# controllerv2e.net
KiCad netlist of a schematic drawn in EAGLE
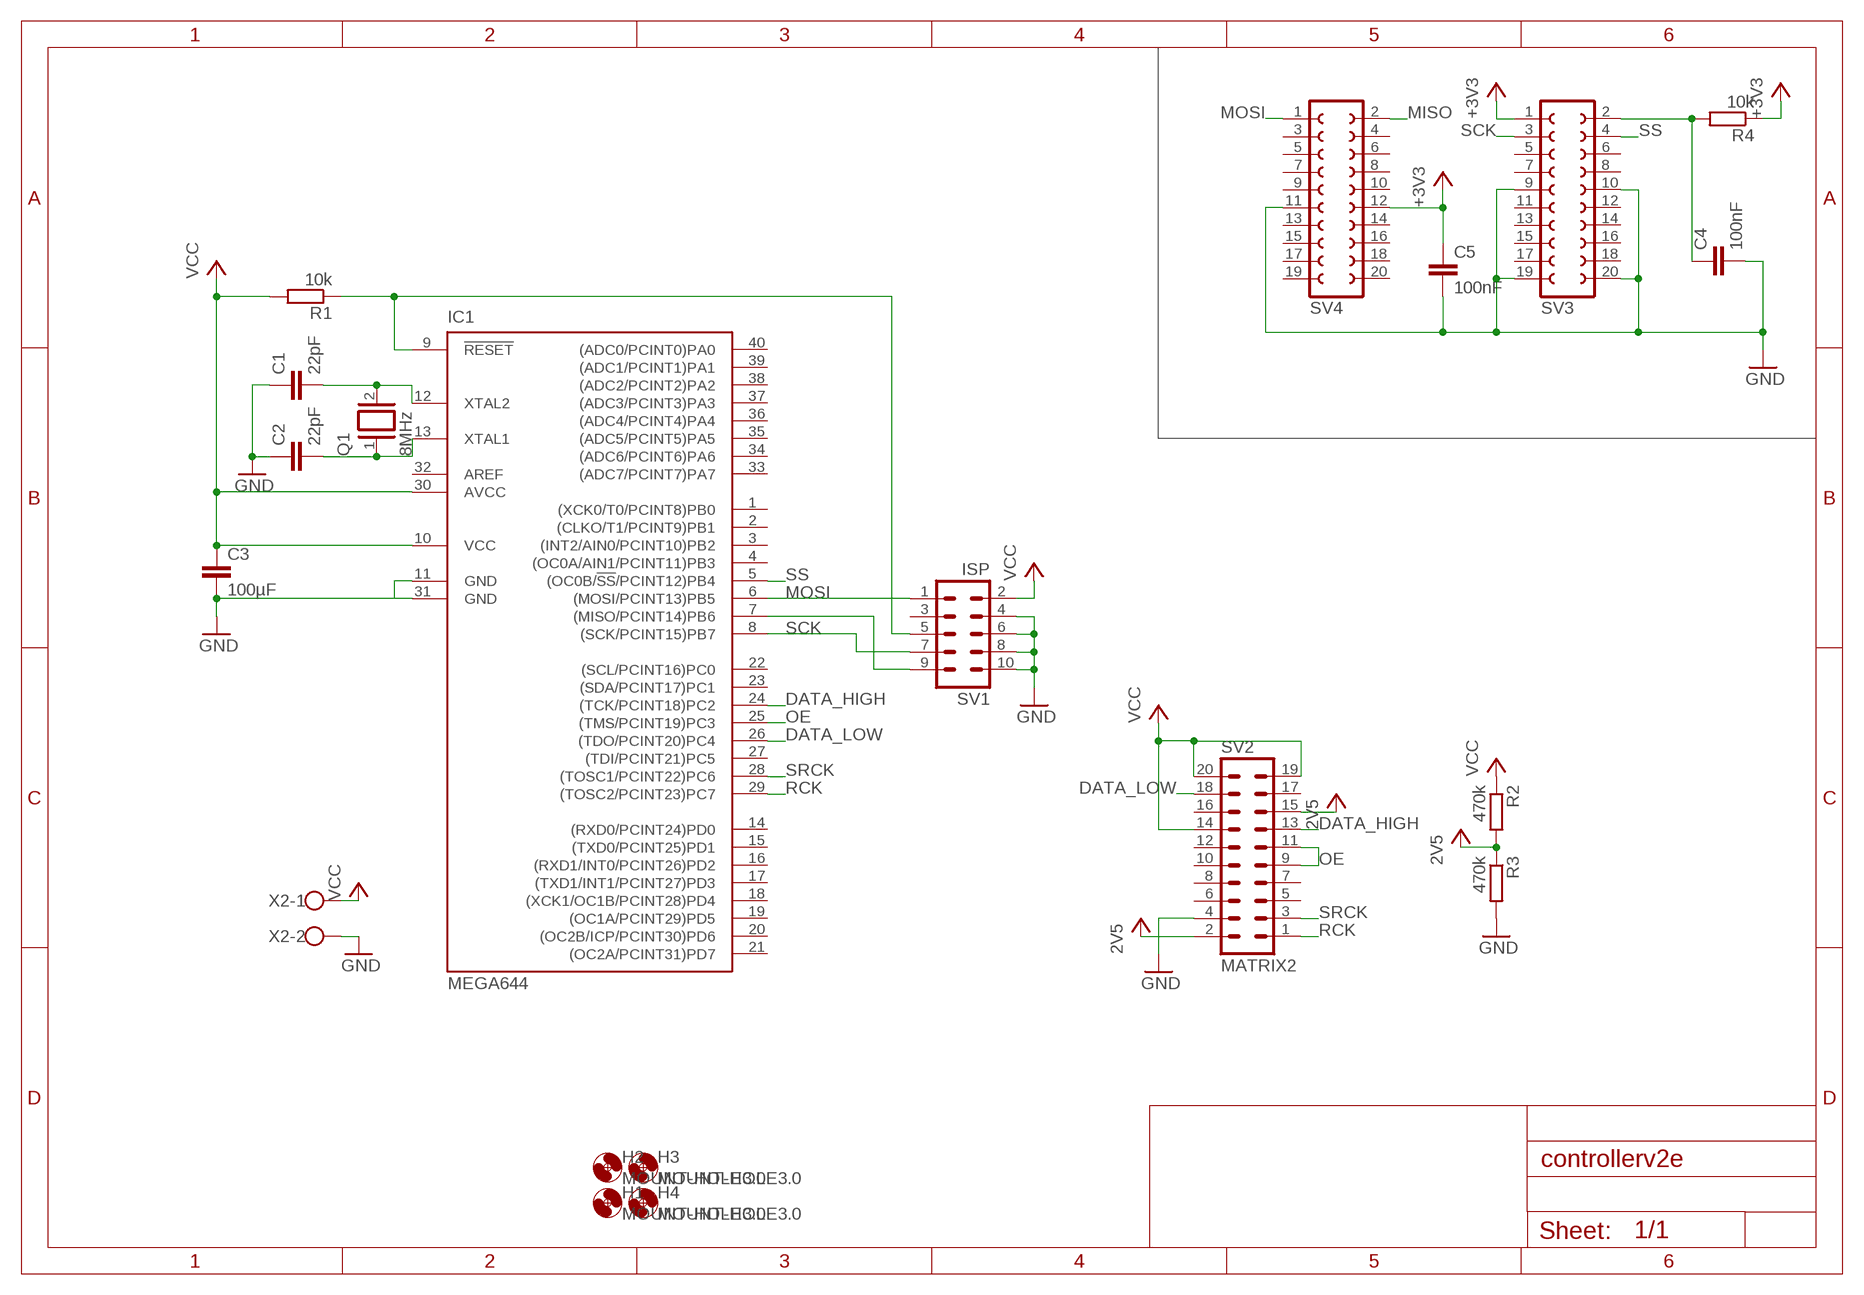
[diagram p0: schematic, sheet 1]

(export (version "E")
  (design (tool "Eeschema 10.0.6"))
  (components
    (comp (ref "C1")
      (value "22pF")
      (footprint "eagle-import:C050-024X044")
      (libsource (lib "eagle-import") (part "C-EU050-024X044"))
    )
    (comp (ref "C2")
      (value "22pF")
      (footprint "eagle-import:C050-024X044")
      (libsource (lib "eagle-import") (part "C-EU050-024X044"))
    )
    (comp (ref "C3")
      (value "100µF")
      (footprint "eagle-import:C050-030X075")
      (libsource (lib "eagle-import") (part "C-EU050-030X075"))
    )
    (comp (ref "C4")
      (value "100nF")
      (footprint "eagle-import:C050-024X044")
      (libsource (lib "eagle-import") (part "C-EU050-024X044"))
    )
    (comp (ref "C5")
      (value "100nF")
      (footprint "eagle-import:C050-024X044")
      (libsource (lib "eagle-import") (part "C-EU050-024X044"))
    )
    (comp (ref "H1")
      (value "MOUNT-HOLE3.0")
      (footprint "eagle-import:3,0")
      (libsource (lib "eagle-import") (part "MOUNT-HOLE3.0"))
    )
    (comp (ref "H2")
      (value "MOUNT-HOLE3.0")
      (footprint "eagle-import:3,0")
      (libsource (lib "eagle-import") (part "MOUNT-HOLE3.0"))
    )
    (comp (ref "H3")
      (value "MOUNT-HOLE3.0")
      (footprint "eagle-import:3,0")
      (libsource (lib "eagle-import") (part "MOUNT-HOLE3.0"))
    )
    (comp (ref "H4")
      (value "MOUNT-HOLE3.0")
      (footprint "eagle-import:3,0")
      (libsource (lib "eagle-import") (part "MOUNT-HOLE3.0"))
    )
    (comp (ref "IC1")
      (value "MEGA644")
      (footprint "eagle-import:DIL40")
      (libsource (lib "eagle-import") (part "MEGA164P/324P/644P-PU"))
    )
    (comp (ref "Q1")
      (value "8MHz")
      (footprint "eagle-import:QS")
      (libsource (lib "eagle-import") (part "XTAL/S"))
    )
    (comp (ref "R1")
      (value "10k")
      (footprint "eagle-import:0207_10")
      (libsource (lib "eagle-import") (part "R-EU_0207/10"))
    )
    (comp (ref "R2")
      (value "470k")
      (footprint "eagle-import:0207_10")
      (libsource (lib "eagle-import") (part "R-EU_0207/10"))
    )
    (comp (ref "R3")
      (value "470k")
      (footprint "eagle-import:0207_10")
      (libsource (lib "eagle-import") (part "R-EU_0207/10"))
    )
    (comp (ref "R4")
      (value "10k")
      (footprint "eagle-import:0207_10")
      (libsource (lib "eagle-import") (part "R-EU_0207/10"))
    )
    (comp (ref "SV1")
      (value "ISP")
      (footprint "eagle-import:ML10")
      (libsource (lib "eagle-import") (part "ML10"))
    )
    (comp (ref "SV2")
      (value "MATRIX2")
      (footprint "eagle-import:ML20")
      (libsource (lib "eagle-import") (part "ML20"))
    )
    (comp (ref "SV3")
      (value "FE10-2")
      (footprint "eagle-import:FE10-2")
      (libsource (lib "eagle-import") (part "FE10-2"))
    )
    (comp (ref "SV4")
      (value "FE10-2")
      (footprint "eagle-import:FE10-2")
      (libsource (lib "eagle-import") (part "FE10-2"))
    )
    (comp (ref "X2")
      (value "GND")
      (footprint "eagle-import:W237-102")
      (fields (field (name "MPN") "237-102"))
      (libsource (lib "eagle-import") (part "W237-102"))
    )
  )
  (nets
    (net (code "1") (name "+3V3") (class "Default")
      (node (ref "C5") (pin "1") (pinfunction "1_1") (pintype "passive"))
      (node (ref "R2") (pin "2") (pinfunction "2_2") (pintype "passive"))
      (node (ref "R3") (pin "1") (pinfunction "1_1") (pintype "passive"))
      (node (ref "R4") (pin "1") (pinfunction "1_1") (pintype "passive"))
      (node (ref "SV2") (pin "15") (pinfunction "15_15") (pintype "passive"))
      (node (ref "SV2") (pin "2") (pinfunction "2_2") (pintype "passive"))
      (node (ref "SV3") (pin "1") (pinfunction "1_1") (pintype "passive"))
      (node (ref "SV4") (pin "12") (pinfunction "12_12") (pintype "passive"))
    )
    (net (code "2") (name "/AREF") (class "Default")
      (node (ref "IC1") (pin "32") (pinfunction "AREF_32") (pintype "power_in"))
    )
    (net (code "3") (name "/DATA_HIGH") (class "Default")
      (node (ref "IC1") (pin "24") (pinfunction "(TCK/PCINT18)PC2_24") (pintype "bidirectional"))
      (node (ref "SV2") (pin "13") (pinfunction "13_13") (pintype "passive"))
    )
    (net (code "4") (name "/DATA_LOW") (class "Default")
      (node (ref "IC1") (pin "26") (pinfunction "(TDO/PCINT20)PC4_26") (pintype "bidirectional"))
      (node (ref "SV2") (pin "18") (pinfunction "18_18") (pintype "passive"))
    )
    (net (code "5") (name "/MISO") (class "Default")
      (node (ref "SV4") (pin "2") (pinfunction "2_2") (pintype "passive"))
    )
    (net (code "6") (name "/MOSI") (class "Default")
      (node (ref "IC1") (pin "6") (pinfunction "(MOSI/PCINT13)PB5_6") (pintype "bidirectional"))
      (node (ref "SV1") (pin "1") (pinfunction "1_1") (pintype "passive"))
      (node (ref "SV4") (pin "1") (pinfunction "1_1") (pintype "passive"))
    )
    (net (code "7") (name "/OE") (class "Default")
      (node (ref "IC1") (pin "25") (pinfunction "(TMS/PCINT19)PC3_25") (pintype "bidirectional"))
      (node (ref "SV2") (pin "11") (pinfunction "11_11") (pintype "passive"))
      (node (ref "SV2") (pin "9") (pinfunction "9_9") (pintype "passive"))
    )
    (net (code "8") (name "/RCK") (class "Default")
      (node (ref "IC1") (pin "29") (pinfunction "(TOSC2/PCINT23)PC7_29") (pintype "bidirectional"))
      (node (ref "SV2") (pin "1") (pinfunction "1_1") (pintype "passive"))
    )
    (net (code "9") (name "/SCK") (class "Default")
      (node (ref "IC1") (pin "8") (pinfunction "(SCK/PCINT15)PB7_8") (pintype "bidirectional"))
      (node (ref "SV1") (pin "7") (pinfunction "7_7") (pintype "passive"))
      (node (ref "SV3") (pin "3") (pinfunction "3_3") (pintype "passive"))
    )
    (net (code "10") (name "/SRCK") (class "Default")
      (node (ref "IC1") (pin "28") (pinfunction "(TOSC1/PCINT22)PC6_28") (pintype "bidirectional"))
      (node (ref "SV2") (pin "3") (pinfunction "3_3") (pintype "passive"))
    )
    (net (code "11") (name "/SS") (class "Default")
      (node (ref "IC1") (pin "5") (pinfunction "(OC0B/~{SS}/PCINT12)PB4_5") (pintype "bidirectional"))
      (node (ref "SV3") (pin "4") (pinfunction "4_4") (pintype "passive"))
    )
    (net (code "12") (name "GND") (class "Default")
      (node (ref "C1") (pin "1") (pinfunction "1_1") (pintype "passive"))
      (node (ref "C2") (pin "1") (pinfunction "1_1") (pintype "passive"))
      (node (ref "C3") (pin "2") (pinfunction "2_2") (pintype "passive"))
      (node (ref "C4") (pin "2") (pinfunction "2_2") (pintype "passive"))
      (node (ref "C5") (pin "2") (pinfunction "2_2") (pintype "passive"))
      (node (ref "IC1") (pin "11") (pinfunction "GND_11") (pintype "power_in"))
      (node (ref "IC1") (pin "31") (pinfunction "GND_31") (pintype "power_in"))
      (node (ref "R3") (pin "2") (pinfunction "2_2") (pintype "passive"))
      (node (ref "SV1") (pin "10") (pinfunction "10_10") (pintype "passive"))
      (node (ref "SV1") (pin "4") (pinfunction "4_4") (pintype "passive"))
      (node (ref "SV1") (pin "6") (pinfunction "6_6") (pintype "passive"))
      (node (ref "SV1") (pin "8") (pinfunction "8_8") (pintype "passive"))
      (node (ref "SV2") (pin "4") (pinfunction "4_4") (pintype "passive"))
      (node (ref "SV3") (pin "10") (pinfunction "10_10") (pintype "passive"))
      (node (ref "SV3") (pin "19") (pinfunction "19_19") (pintype "passive"))
      (node (ref "SV3") (pin "20") (pinfunction "20_20") (pintype "passive"))
      (node (ref "SV3") (pin "9") (pinfunction "9_9") (pintype "passive"))
      (node (ref "SV4") (pin "11") (pinfunction "11_11") (pintype "passive"))
      (node (ref "X2") (pin "2") (pinfunction "KL_2") (pintype "passive"))
    )
    (net (code "13") (name "Net-(C4-Pad1)") (class "Default")
      (node (ref "C4") (pin "1") (pinfunction "1_1") (pintype "passive"))
      (node (ref "R4") (pin "2") (pinfunction "2_2") (pintype "passive"))
      (node (ref "SV3") (pin "2") (pinfunction "2_2") (pintype "passive"))
    )
    (net (code "14") (name "Net-(IC1-(MISO{slash}PCINT14)PB6)") (class "Default")
      (node (ref "IC1") (pin "7") (pinfunction "(MISO/PCINT14)PB6_7") (pintype "bidirectional"))
      (node (ref "SV1") (pin "9") (pinfunction "9_9") (pintype "passive"))
    )
    (net (code "15") (name "Net-(IC1-XTAL1)") (class "Default")
      (node (ref "C2") (pin "2") (pinfunction "2_2") (pintype "passive"))
      (node (ref "IC1") (pin "13") (pinfunction "XTAL1_13") (pintype "input"))
      (node (ref "Q1") (pin "1") (pinfunction "1_1") (pintype "passive"))
    )
    (net (code "16") (name "Net-(IC1-XTAL2)") (class "Default")
      (node (ref "C1") (pin "2") (pinfunction "2_2") (pintype "passive"))
      (node (ref "IC1") (pin "12") (pinfunction "XTAL2_12") (pintype "output"))
      (node (ref "Q1") (pin "2") (pinfunction "2_2") (pintype "passive"))
    )
    (net (code "17") (name "Net-(IC1-~{RESET})") (class "Default")
      (node (ref "IC1") (pin "9") (pinfunction "~{RESET}_9") (pintype "input"))
      (node (ref "R1") (pin "1") (pinfunction "1_1") (pintype "passive"))
      (node (ref "SV1") (pin "5") (pinfunction "5_5") (pintype "passive"))
    )
    (net (code "18") (name "VCC") (class "Default")
      (node (ref "C3") (pin "1") (pinfunction "1_1") (pintype "passive"))
      (node (ref "IC1") (pin "10") (pinfunction "VCC_10") (pintype "power_in"))
      (node (ref "IC1") (pin "30") (pinfunction "AVCC_30") (pintype "power_in"))
      (node (ref "R1") (pin "2") (pinfunction "2_2") (pintype "passive"))
      (node (ref "R2") (pin "1") (pinfunction "1_1") (pintype "passive"))
      (node (ref "SV1") (pin "2") (pinfunction "2_2") (pintype "passive"))
      (node (ref "SV2") (pin "14") (pinfunction "14_14") (pintype "passive"))
      (node (ref "SV2") (pin "19") (pinfunction "19_19") (pintype "passive"))
      (node (ref "SV2") (pin "20") (pinfunction "20_20") (pintype "passive"))
      (node (ref "X2") (pin "1") (pinfunction "KL_1") (pintype "passive"))
    )
    (net (code "19") (name "unconnected-(IC1-(ADC0{slash}PCINT0)PA0-Pad40)") (class "Default")
      (node (ref "IC1") (pin "40") (pinfunction "(ADC0/PCINT0)PA0_40") (pintype "bidirectional"))
    )
    (net (code "20") (name "unconnected-(IC1-(ADC1{slash}PCINT1)PA1-Pad39)") (class "Default")
      (node (ref "IC1") (pin "39") (pinfunction "(ADC1/PCINT1)PA1_39") (pintype "bidirectional"))
    )
    (net (code "21") (name "unconnected-(IC1-(ADC2{slash}PCINT2)PA2-Pad38)") (class "Default")
      (node (ref "IC1") (pin "38") (pinfunction "(ADC2/PCINT2)PA2_38") (pintype "bidirectional"))
    )
    (net (code "22") (name "unconnected-(IC1-(ADC3{slash}PCINT3)PA3-Pad37)") (class "Default")
      (node (ref "IC1") (pin "37") (pinfunction "(ADC3/PCINT3)PA3_37") (pintype "bidirectional"))
    )
    (net (code "23") (name "unconnected-(IC1-(ADC4{slash}PCINT4)PA4-Pad36)") (class "Default")
      (node (ref "IC1") (pin "36") (pinfunction "(ADC4/PCINT4)PA4_36") (pintype "bidirectional"))
    )
    (net (code "24") (name "unconnected-(IC1-(ADC5{slash}PCINT5)PA5-Pad35)") (class "Default")
      (node (ref "IC1") (pin "35") (pinfunction "(ADC5/PCINT5)PA5_35") (pintype "bidirectional"))
    )
    (net (code "25") (name "unconnected-(IC1-(ADC6{slash}PCINT6)PA6-Pad34)") (class "Default")
      (node (ref "IC1") (pin "34") (pinfunction "(ADC6/PCINT6)PA6_34") (pintype "bidirectional"))
    )
    (net (code "26") (name "unconnected-(IC1-(ADC7{slash}PCINT7)PA7-Pad33)") (class "Default")
      (node (ref "IC1") (pin "33") (pinfunction "(ADC7/PCINT7)PA7_33") (pintype "bidirectional"))
    )
    (net (code "27") (name "unconnected-(IC1-(CLKO{slash}T1{slash}PCINT9)PB1-Pad2)") (class "Default")
      (node (ref "IC1") (pin "2") (pinfunction "(CLKO/T1/PCINT9)PB1_2") (pintype "bidirectional"))
    )
    (net (code "28") (name "unconnected-(IC1-(INT2{slash}AIN0{slash}PCINT10)PB2-Pad3)") (class "Default")
      (node (ref "IC1") (pin "3") (pinfunction "(INT2/AIN0/PCINT10)PB2_3") (pintype "bidirectional"))
    )
    (net (code "29") (name "unconnected-(IC1-(OC0A{slash}AIN1{slash}PCINT11)PB3-Pad4)") (class "Default")
      (node (ref "IC1") (pin "4") (pinfunction "(OC0A/AIN1/PCINT11)PB3_4") (pintype "bidirectional"))
    )
    (net (code "30") (name "unconnected-(IC1-(OC1A{slash}PCINT29)PD5-Pad19)") (class "Default")
      (node (ref "IC1") (pin "19") (pinfunction "(OC1A/PCINT29)PD5_19") (pintype "bidirectional"))
    )
    (net (code "31") (name "unconnected-(IC1-(OC2A{slash}PCINT31)PD7-Pad21)") (class "Default")
      (node (ref "IC1") (pin "21") (pinfunction "(OC2A/PCINT31)PD7_21") (pintype "bidirectional"))
    )
    (net (code "32") (name "unconnected-(IC1-(OC2B{slash}ICP{slash}PCINT30)PD6-Pad20)") (class "Default")
      (node (ref "IC1") (pin "20") (pinfunction "(OC2B/ICP/PCINT30)PD6_20") (pintype "bidirectional"))
    )
    (net (code "33") (name "unconnected-(IC1-(RXD0{slash}PCINT24)PD0-Pad14)") (class "Default")
      (node (ref "IC1") (pin "14") (pinfunction "(RXD0/PCINT24)PD0_14") (pintype "bidirectional"))
    )
    (net (code "34") (name "unconnected-(IC1-(RXD1{slash}INT0{slash}PCINT26)PD2-Pad16)") (class "Default")
      (node (ref "IC1") (pin "16") (pinfunction "(RXD1/INT0/PCINT26)PD2_16") (pintype "bidirectional"))
    )
    (net (code "35") (name "unconnected-(IC1-(SCL{slash}PCINT16)PC0-Pad22)") (class "Default")
      (node (ref "IC1") (pin "22") (pinfunction "(SCL/PCINT16)PC0_22") (pintype "bidirectional"))
    )
    (net (code "36") (name "unconnected-(IC1-(SDA{slash}PCINT17)PC1-Pad23)") (class "Default")
      (node (ref "IC1") (pin "23") (pinfunction "(SDA/PCINT17)PC1_23") (pintype "bidirectional"))
    )
    (net (code "37") (name "unconnected-(IC1-(TDI{slash}PCINT21)PC5-Pad27)") (class "Default")
      (node (ref "IC1") (pin "27") (pinfunction "(TDI/PCINT21)PC5_27") (pintype "bidirectional"))
    )
    (net (code "38") (name "unconnected-(IC1-(TXD0{slash}PCINT25)PD1-Pad15)") (class "Default")
      (node (ref "IC1") (pin "15") (pinfunction "(TXD0/PCINT25)PD1_15") (pintype "bidirectional"))
    )
    (net (code "39") (name "unconnected-(IC1-(TXD1{slash}INT1{slash}PCINT27)PD3-Pad17)") (class "Default")
      (node (ref "IC1") (pin "17") (pinfunction "(TXD1/INT1/PCINT27)PD3_17") (pintype "bidirectional"))
    )
    (net (code "40") (name "unconnected-(IC1-(XCK0{slash}T0{slash}PCINT8)PB0-Pad1)") (class "Default")
      (node (ref "IC1") (pin "1") (pinfunction "(XCK0/T0/PCINT8)PB0_1") (pintype "bidirectional"))
    )
    (net (code "41") (name "unconnected-(IC1-(XCK1{slash}OC1B{slash}PCINT28)PD4-Pad18)") (class "Default")
      (node (ref "IC1") (pin "18") (pinfunction "(XCK1/OC1B/PCINT28)PD4_18") (pintype "bidirectional"))
    )
    (net (code "42") (name "unconnected-(SV1-Pad3)") (class "Default")
      (node (ref "SV1") (pin "3") (pinfunction "3_3") (pintype "passive"))
    )
    (net (code "43") (name "unconnected-(SV2-Pad5)") (class "Default")
      (node (ref "SV2") (pin "5") (pinfunction "5_5") (pintype "passive"))
    )
    (net (code "44") (name "unconnected-(SV2-Pad6)") (class "Default")
      (node (ref "SV2") (pin "6") (pinfunction "6_6") (pintype "passive"))
    )
    (net (code "45") (name "unconnected-(SV2-Pad7)") (class "Default")
      (node (ref "SV2") (pin "7") (pinfunction "7_7") (pintype "passive"))
    )
    (net (code "46") (name "unconnected-(SV2-Pad8)") (class "Default")
      (node (ref "SV2") (pin "8") (pinfunction "8_8") (pintype "passive"))
    )
    (net (code "47") (name "unconnected-(SV2-Pad10)") (class "Default")
      (node (ref "SV2") (pin "10") (pinfunction "10_10") (pintype "passive"))
    )
    (net (code "48") (name "unconnected-(SV2-Pad12)") (class "Default")
      (node (ref "SV2") (pin "12") (pinfunction "12_12") (pintype "passive"))
    )
    (net (code "49") (name "unconnected-(SV2-Pad16)") (class "Default")
      (node (ref "SV2") (pin "16") (pinfunction "16_16") (pintype "passive"))
    )
    (net (code "50") (name "unconnected-(SV2-Pad17)") (class "Default")
      (node (ref "SV2") (pin "17") (pinfunction "17_17") (pintype "passive"))
    )
    (net (code "51") (name "unconnected-(SV3-Pad5)") (class "Default")
      (node (ref "SV3") (pin "5") (pinfunction "5_5") (pintype "passive"))
    )
    (net (code "52") (name "unconnected-(SV3-Pad6)") (class "Default")
      (node (ref "SV3") (pin "6") (pinfunction "6_6") (pintype "passive"))
    )
    (net (code "53") (name "unconnected-(SV3-Pad7)") (class "Default")
      (node (ref "SV3") (pin "7") (pinfunction "7_7") (pintype "passive"))
    )
    (net (code "54") (name "unconnected-(SV3-Pad8)") (class "Default")
      (node (ref "SV3") (pin "8") (pinfunction "8_8") (pintype "passive"))
    )
    (net (code "55") (name "unconnected-(SV3-Pad11)") (class "Default")
      (node (ref "SV3") (pin "11") (pinfunction "11_11") (pintype "passive"))
    )
    (net (code "56") (name "unconnected-(SV3-Pad12)") (class "Default")
      (node (ref "SV3") (pin "12") (pinfunction "12_12") (pintype "passive"))
    )
    (net (code "57") (name "unconnected-(SV3-Pad13)") (class "Default")
      (node (ref "SV3") (pin "13") (pinfunction "13_13") (pintype "passive"))
    )
    (net (code "58") (name "unconnected-(SV3-Pad14)") (class "Default")
      (node (ref "SV3") (pin "14") (pinfunction "14_14") (pintype "passive"))
    )
    (net (code "59") (name "unconnected-(SV3-Pad15)") (class "Default")
      (node (ref "SV3") (pin "15") (pinfunction "15_15") (pintype "passive"))
    )
    (net (code "60") (name "unconnected-(SV3-Pad16)") (class "Default")
      (node (ref "SV3") (pin "16") (pinfunction "16_16") (pintype "passive"))
    )
    (net (code "61") (name "unconnected-(SV3-Pad17)") (class "Default")
      (node (ref "SV3") (pin "17") (pinfunction "17_17") (pintype "passive"))
    )
    (net (code "62") (name "unconnected-(SV3-Pad18)") (class "Default")
      (node (ref "SV3") (pin "18") (pinfunction "18_18") (pintype "passive"))
    )
    (net (code "63") (name "unconnected-(SV4-Pad3)") (class "Default")
      (node (ref "SV4") (pin "3") (pinfunction "3_3") (pintype "passive"))
    )
    (net (code "64") (name "unconnected-(SV4-Pad4)") (class "Default")
      (node (ref "SV4") (pin "4") (pinfunction "4_4") (pintype "passive"))
    )
    (net (code "65") (name "unconnected-(SV4-Pad5)") (class "Default")
      (node (ref "SV4") (pin "5") (pinfunction "5_5") (pintype "passive"))
    )
    (net (code "66") (name "unconnected-(SV4-Pad6)") (class "Default")
      (node (ref "SV4") (pin "6") (pinfunction "6_6") (pintype "passive"))
    )
    (net (code "67") (name "unconnected-(SV4-Pad7)") (class "Default")
      (node (ref "SV4") (pin "7") (pinfunction "7_7") (pintype "passive"))
    )
    (net (code "68") (name "unconnected-(SV4-Pad8)") (class "Default")
      (node (ref "SV4") (pin "8") (pinfunction "8_8") (pintype "passive"))
    )
    (net (code "69") (name "unconnected-(SV4-Pad9)") (class "Default")
      (node (ref "SV4") (pin "9") (pinfunction "9_9") (pintype "passive"))
    )
    (net (code "70") (name "unconnected-(SV4-Pad10)") (class "Default")
      (node (ref "SV4") (pin "10") (pinfunction "10_10") (pintype "passive"))
    )
    (net (code "71") (name "unconnected-(SV4-Pad13)") (class "Default")
      (node (ref "SV4") (pin "13") (pinfunction "13_13") (pintype "passive"))
    )
    (net (code "72") (name "unconnected-(SV4-Pad14)") (class "Default")
      (node (ref "SV4") (pin "14") (pinfunction "14_14") (pintype "passive"))
    )
    (net (code "73") (name "unconnected-(SV4-Pad15)") (class "Default")
      (node (ref "SV4") (pin "15") (pinfunction "15_15") (pintype "passive"))
    )
    (net (code "74") (name "unconnected-(SV4-Pad16)") (class "Default")
      (node (ref "SV4") (pin "16") (pinfunction "16_16") (pintype "passive"))
    )
    (net (code "75") (name "unconnected-(SV4-Pad17)") (class "Default")
      (node (ref "SV4") (pin "17") (pinfunction "17_17") (pintype "passive"))
    )
    (net (code "76") (name "unconnected-(SV4-Pad18)") (class "Default")
      (node (ref "SV4") (pin "18") (pinfunction "18_18") (pintype "passive"))
    )
    (net (code "77") (name "unconnected-(SV4-Pad19)") (class "Default")
      (node (ref "SV4") (pin "19") (pinfunction "19_19") (pintype "passive"))
    )
    (net (code "78") (name "unconnected-(SV4-Pad20)") (class "Default")
      (node (ref "SV4") (pin "20") (pinfunction "20_20") (pintype "passive"))
    )
  )
)
